# Test1.net
KiCad netlist of a schematic drawn in EAGLE
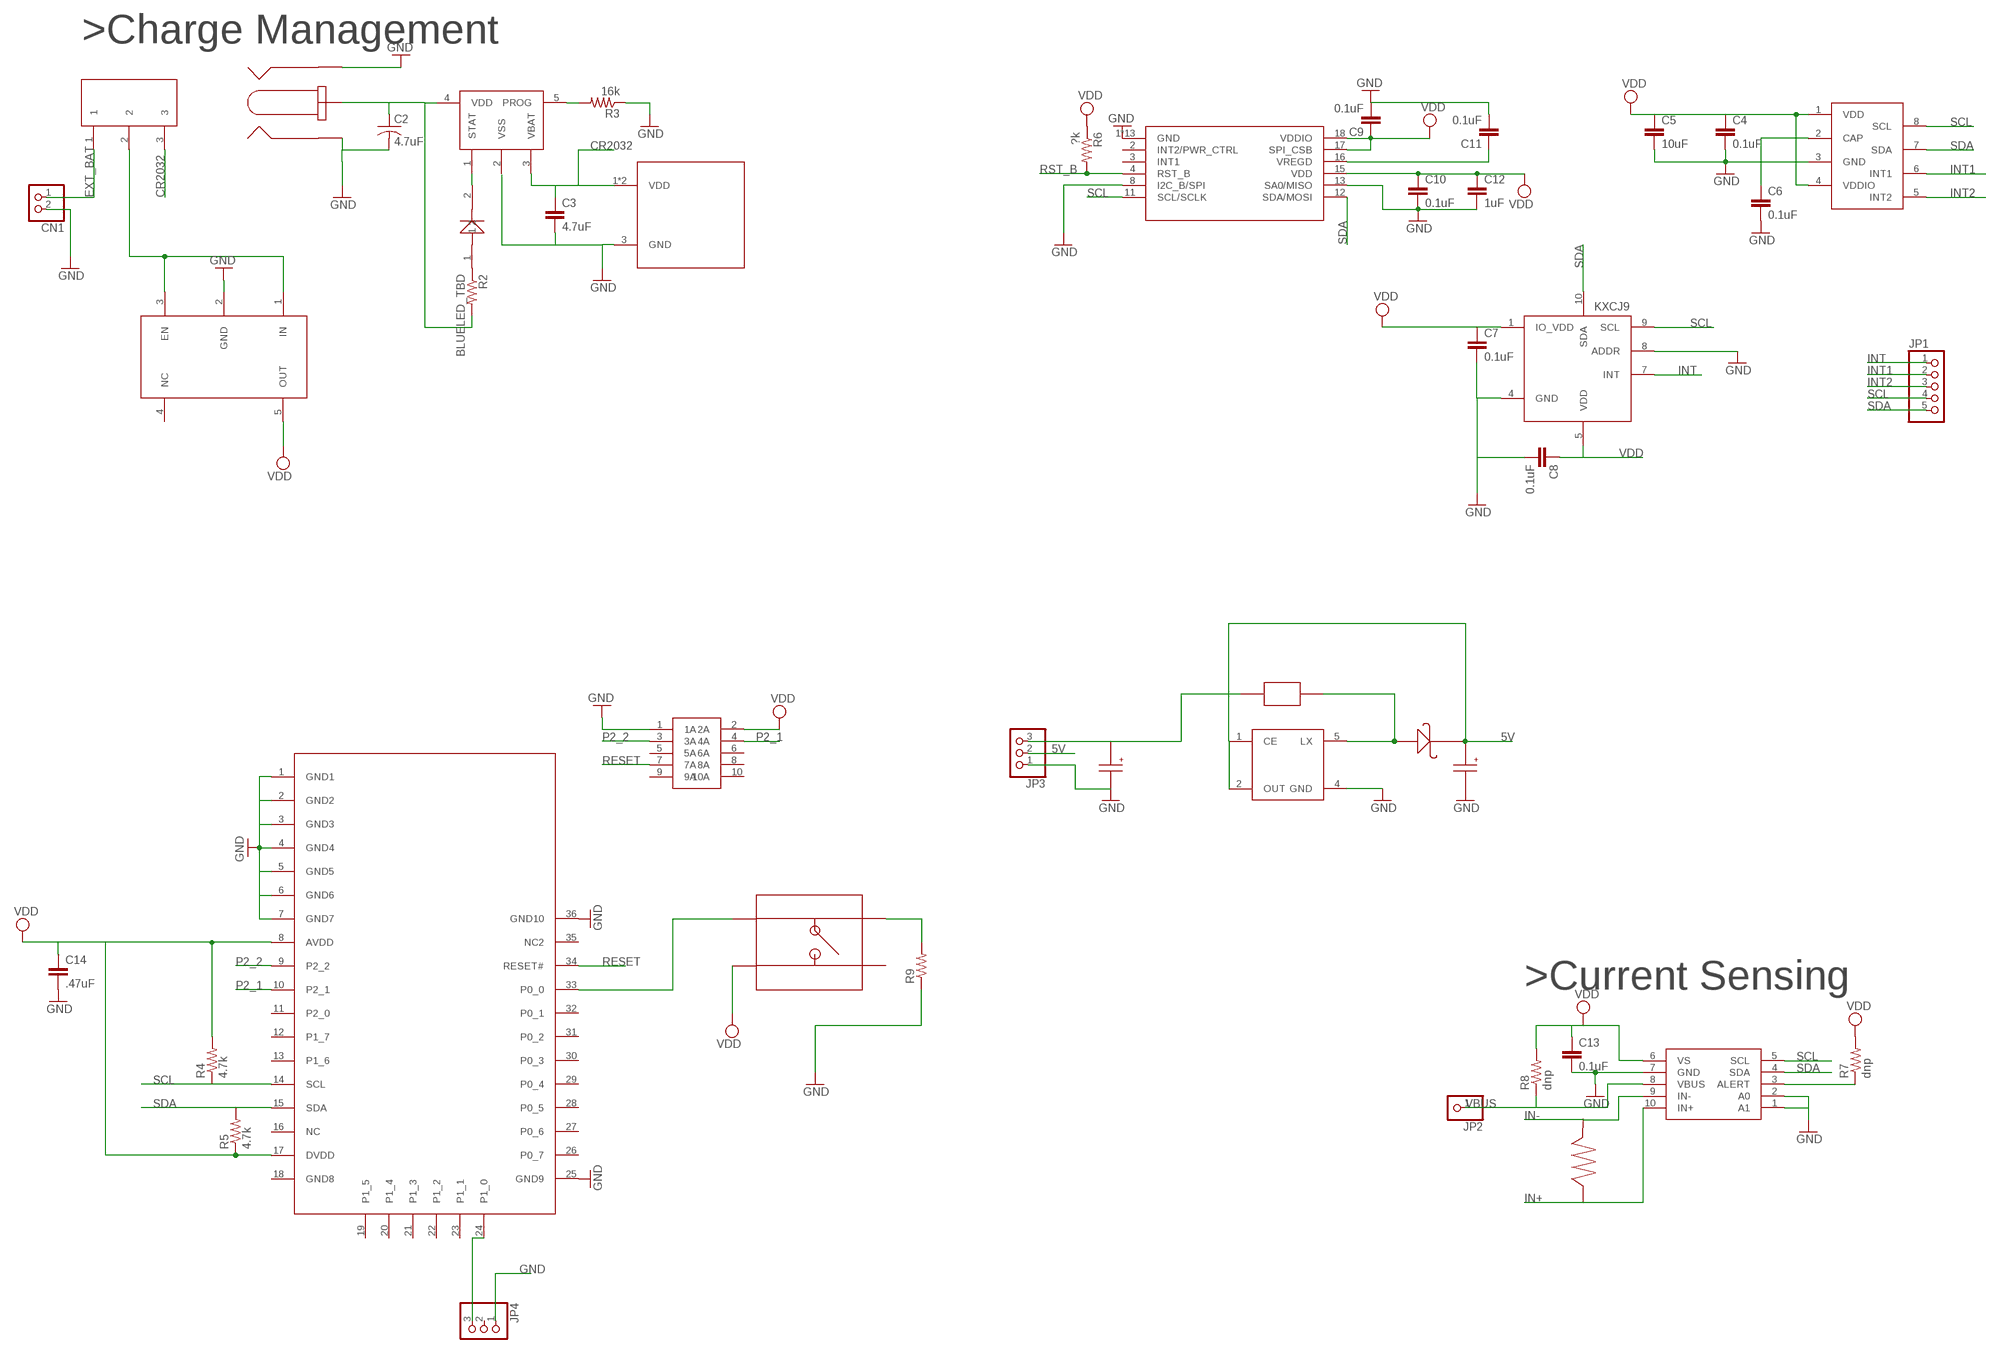
[diagram p0: schematic, sheet 1]

(export (version "E")
  (design (tool "Eeschema 10.0.6"))
  (components
    (comp (ref "C2")
      (value "4.7uF")
      (footprint "eagle-import:C0603")
      (libsource (lib "eagle-import") (part "C-USC0603"))
    )
    (comp (ref "C3")
      (value "4.7uF")
      (footprint "eagle-import:C0402")
      (libsource (lib "eagle-import") (part "C-EUC0402"))
    )
    (comp (ref "C4")
      (value "0.1uF")
      (footprint "eagle-import:C0402")
      (libsource (lib "eagle-import") (part "C-EUC0402"))
    )
    (comp (ref "C5")
      (value "10uF")
      (footprint "eagle-import:C0402")
      (libsource (lib "eagle-import") (part "C-EUC0402"))
    )
    (comp (ref "C6")
      (value "0.1uF")
      (footprint "eagle-import:C0402")
      (libsource (lib "eagle-import") (part "C-EUC0402"))
    )
    (comp (ref "C7")
      (value "0.1uF")
      (footprint "eagle-import:C0402")
      (libsource (lib "eagle-import") (part "C-EUC0402"))
    )
    (comp (ref "C8")
      (value "0.1uF")
      (footprint "eagle-import:C0402")
      (libsource (lib "eagle-import") (part "C-EUC0402"))
    )
    (comp (ref "C9")
      (value "0.1uF")
      (footprint "eagle-import:C0402")
      (libsource (lib "eagle-import") (part "C-EUC0402"))
    )
    (comp (ref "C10")
      (value "0.1uF")
      (footprint "eagle-import:C0402")
      (libsource (lib "eagle-import") (part "C-EUC0402"))
    )
    (comp (ref "C11")
      (value "0.1uF")
      (footprint "eagle-import:C0402")
      (libsource (lib "eagle-import") (part "C-EUC0402"))
    )
    (comp (ref "C12")
      (value "1uF")
      (footprint "eagle-import:C0402")
      (libsource (lib "eagle-import") (part "C-EUC0402"))
    )
    (comp (ref "C13")
      (value "0.1uF")
      (footprint "eagle-import:C0402")
      (libsource (lib "eagle-import") (part "C-EUC0402"))
    )
    (comp (ref "C14")
      (value ".47uF")
      (footprint "eagle-import:C0402")
      (libsource (lib "eagle-import") (part "C-EUC0402"))
    )
    (comp (ref "CN1")
      (value "JST_2PIN-THM")
      (footprint "eagle-import:JST-PH-2-THM")
      (libsource (lib "eagle-import") (part "JST_2PIN-THM"))
    )
    (comp (ref "JP1")
      (value "PINHD-1X5")
      (footprint "eagle-import:1X05")
      (libsource (lib "eagle-import") (part "PINHD-1X5"))
    )
    (comp (ref "JP2")
      (value "PINHD-1X1")
      (footprint "eagle-import:1X01")
      (libsource (lib "eagle-import") (part "PINHD-1X1"))
    )
    (comp (ref "JP3")
      (value "PINHD-1X3")
      (footprint "eagle-import:1X03")
      (libsource (lib "eagle-import") (part "PINHD-1X3"))
    )
    (comp (ref "JP4")
      (value "PINHD-1X3/90")
      (footprint "eagle-import:1X03_90")
      (libsource (lib "eagle-import") (part "PINHD-1X3/90"))
    )
    (comp (ref "R2")
      (value "BLUELED_TBD")
      (footprint "eagle-import:R0402")
      (libsource (lib "eagle-import") (part "R-US_R0402"))
    )
    (comp (ref "R3")
      (value "16k")
      (footprint "eagle-import:R0402")
      (libsource (lib "eagle-import") (part "R-US_R0402"))
    )
    (comp (ref "R4")
      (value "4.7k")
      (footprint "eagle-import:R0402")
      (libsource (lib "eagle-import") (part "R-US_R0402"))
    )
    (comp (ref "R5")
      (value "4.7k")
      (footprint "eagle-import:R0402")
      (libsource (lib "eagle-import") (part "R-US_R0402"))
    )
    (comp (ref "R6")
      (value "?k")
      (footprint "eagle-import:R0402")
      (libsource (lib "eagle-import") (part "R-US_R0402"))
    )
    (comp (ref "R7")
      (value "dnp")
      (footprint "eagle-import:R0402")
      (libsource (lib "eagle-import") (part "R-US_R0402"))
    )
    (comp (ref "R8")
      (value "dnp")
      (footprint "eagle-import:R0402")
      (libsource (lib "eagle-import") (part "R-US_R0402"))
    )
    (comp (ref "R9")
      (value "R-US_R0402")
      (footprint "eagle-import:R0402")
      (libsource (lib "eagle-import") (part "R-US_R0402"))
    )
    (comp (ref "U$1")
      (value "BAT-HLD-001")
      (footprint "eagle-import:BAT-HLD-001")
      (libsource (lib "eagle-import") (part "BAT-HLD-001"))
    )
    (comp (ref "U$2")
      (value "INA226")
      (footprint "eagle-import:INA226")
      (libsource (lib "eagle-import") (part "INA226"))
    )
    (comp (ref "U$3")
      (value "FXAS21002")
      (footprint "eagle-import:FXAS21002")
      (libsource (lib "eagle-import") (part "FXAS21002"))
    )
    (comp (ref "U$4")
      (value "PJ-040")
      (footprint "eagle-import:PJ-040")
      (libsource (lib "eagle-import") (part "PJ-040"))
    )
    (comp (ref "U$5")
      (value "PTS840")
      (footprint "eagle-import:PTS840")
      (libsource (lib "eagle-import") (part "PTS840"))
    )
    (comp (ref "U$6")
      (value "CD54NP-470LC")
      (footprint "eagle-import:CD54NP-470LC")
      (libsource (lib "eagle-import") (part "CD54NP-470LC"))
    )
    (comp (ref "U$7")
      (value "MRB0520LT1G")
      (footprint "eagle-import:SOD-323F")
      (libsource (lib "eagle-import") (part "MRB0520LT1G"))
    )
    (comp (ref "U$8")
      (value "MIC5203")
      (footprint "eagle-import:SOT23-5L")
      (libsource (lib "eagle-import") (part "MIC5203"))
    )
    (comp (ref "U$9")
      (value "MLP3115A2")
      (footprint "eagle-import:MLP3115A2")
      (libsource (lib "eagle-import") (part "MLP3115A2"))
    )
    (comp (ref "U$10")
      (value "RIBBON_10POS_MALE")
      (footprint "eagle-import:RIBBON_10POS_MALE")
      (libsource (lib "eagle-import") (part "RIBBON_10POS_MALE"))
    )
    (comp (ref "U$11")
      (value "BLE113")
      (footprint "eagle-import:BLUEGIGA")
      (libsource (lib "eagle-import") (part "BLE113"))
    )
    (comp (ref "U$12")
      (value "SPDT_THRU")
      (footprint "eagle-import:SPDT_THRU")
      (libsource (lib "eagle-import") (part "SPDT_THRU"))
    )
    (comp (ref "U$13")
      (value "KXCJ9")
      (footprint "eagle-import:KXCJ9")
      (libsource (lib "eagle-import") (part "KXCJ9"))
    )
    (comp (ref "U$14")
      (value "LTST-C190KRKT")
      (footprint "eagle-import:LTST-C190KRKT")
      (libsource (lib "eagle-import") (part "LTST-C190KRKT"))
    )
    (comp (ref "U$15")
      (value "ERJ-MS6SFM50U")
      (footprint "eagle-import:ERJ-MS6SFM50U")
      (libsource (lib "eagle-import") (part "ERJ-MS6SFM50U"))
    )
    (comp (ref "U$16")
      (value "MCP73831")
      (footprint "eagle-import:MCP73831")
      (libsource (lib "eagle-import") (part "MCP73831"))
    )
    (comp (ref "U$17")
      (value "NCP1402")
      (footprint "eagle-import:SOT23-5L")
      (libsource (lib "eagle-import") (part "NCP1402"))
    )
    (comp (ref "U$18")
      (value "10uF")
      (footprint "eagle-import:C2413")
      (libsource (lib "eagle-import") (part "C2413"))
    )
    (comp (ref "U$19")
      (value "68uF")
      (footprint "eagle-import:C2413")
      (libsource (lib "eagle-import") (part "C2413"))
    )
  )
  (nets
    (net (code "1") (name "/5V") (class "Default")
      (node (ref "JP3") (pin "2") (pinfunction "2_2") (pintype "passive"))
      (node (ref "U$17") (pin "1") (pinfunction "CE_1") (pintype "bidirectional"))
      (node (ref "U$17") (pin "2") (pinfunction "OUT_2") (pintype "bidirectional"))
      (node (ref "U$19") (pin "1") (pinfunction "P$1_1") (pintype "bidirectional"))
      (node (ref "U$7") (pin "2") (pinfunction "P$2_2") (pintype "bidirectional"))
    )
    (net (code "2") (name "/CR2032") (class "Default")
      (node (ref "C3") (pin "1") (pinfunction "1_1") (pintype "passive"))
      (node (ref "U$1") (pin "1") (pinfunction "VDD_1") (pintype "bidirectional"))
      (node (ref "U$1") (pin "2") (pinfunction "VDD_2") (pintype "bidirectional"))
      (node (ref "U$12") (pin "3") (pinfunction "3_3") (pintype "bidirectional"))
      (node (ref "U$16") (pin "3") (pinfunction "VBAT_3") (pintype "bidirectional"))
    )
    (net (code "3") (name "/EXT_BAT") (class "Default")
      (node (ref "CN1") (pin "1") (pinfunction "2_1") (pintype "passive"))
      (node (ref "U$12") (pin "1") (pinfunction "1_1") (pintype "bidirectional"))
    )
    (net (code "4") (name "/IN+") (class "Default")
      (node (ref "U$15") (pin "1") (pinfunction "P$1_1") (pintype "bidirectional"))
      (node (ref "U$2") (pin "10") (pinfunction "IN+_10") (pintype "bidirectional"))
    )
    (net (code "5") (name "/IN-") (class "Default")
      (node (ref "U$15") (pin "2") (pinfunction "P$2_2") (pintype "bidirectional"))
      (node (ref "U$2") (pin "9") (pinfunction "IN-_9") (pintype "bidirectional"))
    )
    (net (code "6") (name "/INT") (class "Default")
      (node (ref "JP1") (pin "1") (pinfunction "1_1") (pintype "passive"))
      (node (ref "U$13") (pin "7") (pinfunction "INT_7") (pintype "bidirectional"))
    )
    (net (code "7") (name "/INT1") (class "Default")
      (node (ref "JP1") (pin "2") (pinfunction "2_2") (pintype "passive"))
      (node (ref "U$9") (pin "6") (pinfunction "INT1_6") (pintype "bidirectional"))
    )
    (net (code "8") (name "/INT2") (class "Default")
      (node (ref "JP1") (pin "3") (pinfunction "3_3") (pintype "passive"))
      (node (ref "U$9") (pin "5") (pinfunction "INT2_5") (pintype "bidirectional"))
    )
    (net (code "9") (name "/P2_1") (class "Default")
      (node (ref "U$10") (pin "4") (pinfunction "4A_4") (pintype "bidirectional"))
      (node (ref "U$11") (pin "10") (pinfunction "P2_1_10") (pintype "bidirectional"))
    )
    (net (code "10") (name "/P2_2") (class "Default")
      (node (ref "U$10") (pin "3") (pinfunction "3A_3") (pintype "bidirectional"))
      (node (ref "U$11") (pin "9") (pinfunction "P2_2_9") (pintype "bidirectional"))
    )
    (net (code "11") (name "/RESET") (class "Default")
      (node (ref "U$10") (pin "7") (pinfunction "7A_7") (pintype "bidirectional"))
      (node (ref "U$11") (pin "34") (pinfunction "RESET#_34") (pintype "bidirectional"))
    )
    (net (code "12") (name "/RST_B") (class "Default")
      (node (ref "R6") (pin "2") (pinfunction "2_2") (pintype "passive"))
      (node (ref "U$3") (pin "4") (pinfunction "RST_B_4") (pintype "bidirectional"))
    )
    (net (code "13") (name "/SCL") (class "Default")
      (node (ref "JP1") (pin "4") (pinfunction "4_4") (pintype "passive"))
      (node (ref "R4") (pin "1") (pinfunction "1_1") (pintype "passive"))
      (node (ref "U$11") (pin "14") (pinfunction "SCL_14") (pintype "bidirectional"))
      (node (ref "U$13") (pin "9") (pinfunction "SCL_9") (pintype "bidirectional"))
      (node (ref "U$2") (pin "5") (pinfunction "SCL_5") (pintype "bidirectional"))
      (node (ref "U$3") (pin "11") (pinfunction "SCL/SCLK_11") (pintype "bidirectional"))
      (node (ref "U$9") (pin "8") (pinfunction "SCL_8") (pintype "bidirectional"))
    )
    (net (code "14") (name "/SDA") (class "Default")
      (node (ref "JP1") (pin "5") (pinfunction "5_5") (pintype "passive"))
      (node (ref "R5") (pin "2") (pinfunction "2_2") (pintype "passive"))
      (node (ref "U$11") (pin "15") (pinfunction "SDA_15") (pintype "bidirectional"))
      (node (ref "U$13") (pin "10") (pinfunction "SDA_10") (pintype "bidirectional"))
      (node (ref "U$2") (pin "4") (pinfunction "SDA_4") (pintype "bidirectional"))
      (node (ref "U$3") (pin "12") (pinfunction "SDA/MOSI_12") (pintype "bidirectional"))
      (node (ref "U$9") (pin "7") (pinfunction "SDA_7") (pintype "bidirectional"))
    )
    (net (code "15") (name "/VBUS") (class "Default")
      (node (ref "JP2") (pin "1") (pinfunction "1_1") (pintype "passive"))
      (node (ref "R8") (pin "1") (pinfunction "1_1") (pintype "passive"))
      (node (ref "U$2") (pin "8") (pinfunction "VBUS_8") (pintype "bidirectional"))
    )
    (net (code "16") (name "GND") (class "Default")
      (node (ref "C10") (pin "2") (pinfunction "2_2") (pintype "passive"))
      (node (ref "C11") (pin "2") (pinfunction "2_2") (pintype "passive"))
      (node (ref "C12") (pin "2") (pinfunction "2_2") (pintype "passive"))
      (node (ref "C13") (pin "2") (pinfunction "2_2") (pintype "passive"))
      (node (ref "C14") (pin "2") (pinfunction "2_2") (pintype "passive"))
      (node (ref "C2") (pin "2") (pinfunction "2_2") (pintype "passive"))
      (node (ref "C3") (pin "2") (pinfunction "2_2") (pintype "passive"))
      (node (ref "C4") (pin "2") (pinfunction "2_2") (pintype "passive"))
      (node (ref "C5") (pin "2") (pinfunction "2_2") (pintype "passive"))
      (node (ref "C6") (pin "2") (pinfunction "2_2") (pintype "passive"))
      (node (ref "C7") (pin "2") (pinfunction "2_2") (pintype "passive"))
      (node (ref "C8") (pin "2") (pinfunction "2_2") (pintype "passive"))
      (node (ref "C9") (pin "2") (pinfunction "2_2") (pintype "passive"))
      (node (ref "CN1") (pin "2") (pinfunction "1_2") (pintype "passive"))
      (node (ref "JP3") (pin "1") (pinfunction "1_1") (pintype "passive"))
      (node (ref "JP4") (pin "1") (pinfunction "1_1") (pintype "passive"))
      (node (ref "R3") (pin "1") (pinfunction "1_1") (pintype "passive"))
      (node (ref "R9") (pin "1") (pinfunction "1_1") (pintype "passive"))
      (node (ref "U$1") (pin "3") (pinfunction "GND_3") (pintype "bidirectional"))
      (node (ref "U$10") (pin "1") (pinfunction "1A_1") (pintype "bidirectional"))
      (node (ref "U$11") (pin "1") (pinfunction "GND1_1") (pintype "bidirectional"))
      (node (ref "U$11") (pin "2") (pinfunction "GND2_2") (pintype "bidirectional"))
      (node (ref "U$11") (pin "25") (pinfunction "GND9_25") (pintype "bidirectional"))
      (node (ref "U$11") (pin "3") (pinfunction "GND3_3") (pintype "bidirectional"))
      (node (ref "U$11") (pin "36") (pinfunction "GND10_36") (pintype "bidirectional"))
      (node (ref "U$11") (pin "4") (pinfunction "GND4_4") (pintype "bidirectional"))
      (node (ref "U$11") (pin "5") (pinfunction "GND5_5") (pintype "bidirectional"))
      (node (ref "U$11") (pin "6") (pinfunction "GND6_6") (pintype "bidirectional"))
      (node (ref "U$11") (pin "7") (pinfunction "GND7_7") (pintype "bidirectional"))
      (node (ref "U$13") (pin "4") (pinfunction "GND_4") (pintype "bidirectional"))
      (node (ref "U$13") (pin "8") (pinfunction "ADDR_8") (pintype "bidirectional"))
      (node (ref "U$17") (pin "4") (pinfunction "GND_4") (pintype "bidirectional"))
      (node (ref "U$18") (pin "2") (pinfunction "P$2_2") (pintype "bidirectional"))
      (node (ref "U$19") (pin "2") (pinfunction "P$2_2") (pintype "bidirectional"))
      (node (ref "U$2") (pin "1") (pinfunction "A1_1") (pintype "bidirectional"))
      (node (ref "U$2") (pin "2") (pinfunction "A0_2") (pintype "bidirectional"))
      (node (ref "U$2") (pin "7") (pinfunction "GND_7") (pintype "bidirectional"))
      (node (ref "U$3") (pin "1") (pinfunction "GND_1") (pintype "bidirectional"))
      (node (ref "U$3") (pin "10") (pinfunction "GND_10") (pintype "bidirectional"))
      (node (ref "U$3") (pin "13") (pinfunction "SA0/MISO_13") (pintype "bidirectional"))
      (node (ref "U$3") (pin "14") (pinfunction "GND_14") (pintype "bidirectional"))
      (node (ref "U$3") (pin "19") (pinfunction "GND_19") (pintype "bidirectional"))
      (node (ref "U$3") (pin "20") (pinfunction "GND_20") (pintype "bidirectional"))
      (node (ref "U$3") (pin "21") (pinfunction "GND_21") (pintype "bidirectional"))
      (node (ref "U$3") (pin "22") (pinfunction "GND_22") (pintype "bidirectional"))
      (node (ref "U$3") (pin "23") (pinfunction "GND_23") (pintype "bidirectional"))
      (node (ref "U$3") (pin "24") (pinfunction "GND_24") (pintype "bidirectional"))
      (node (ref "U$3") (pin "5") (pinfunction "GND_5") (pintype "bidirectional"))
      (node (ref "U$3") (pin "6") (pinfunction "GND_6") (pintype "bidirectional"))
      (node (ref "U$3") (pin "7") (pinfunction "GND_7") (pintype "bidirectional"))
      (node (ref "U$3") (pin "8") (pinfunction "I2C_B/SPI_8") (pintype "bidirectional"))
      (node (ref "U$3") (pin "9") (pinfunction "GND_9") (pintype "bidirectional"))
      (node (ref "U$4") (pin "2") (pinfunction "2_2") (pintype "bidirectional"))
      (node (ref "U$4") (pin "3") (pinfunction "3_3") (pintype "bidirectional"))
      (node (ref "U$8") (pin "2") (pinfunction "GND_2") (pintype "bidirectional"))
      (node (ref "U$9") (pin "3") (pinfunction "GND_3") (pintype "bidirectional"))
    )
    (net (code "17") (name "Net-(R2-Pad1)") (class "Default")
      (node (ref "R2") (pin "1") (pinfunction "1_1") (pintype "passive"))
      (node (ref "U$14") (pin "1") (pinfunction "1_1") (pintype "bidirectional"))
    )
    (net (code "18") (name "Net-(R9-Pad2)") (class "Default")
      (node (ref "R9") (pin "2") (pinfunction "2_2") (pintype "passive"))
      (node (ref "U$5") (pin "3") (pinfunction "3_3") (pintype "bidirectional"))
    )
    (net (code "19") (name "Net-(U$2-ALERT)") (class "Default")
      (node (ref "R7") (pin "1") (pinfunction "1_1") (pintype "passive"))
      (node (ref "U$2") (pin "3") (pinfunction "ALERT_3") (pintype "bidirectional"))
    )
    (net (code "20") (name "Net-(U$3-VREGD)") (class "Default")
      (node (ref "C11") (pin "1") (pinfunction "1_1") (pintype "passive"))
      (node (ref "U$3") (pin "16") (pinfunction "VREGD_16") (pintype "bidirectional"))
    )
    (net (code "21") (name "Net-(U$8-EN)") (class "Default")
      (node (ref "U$12") (pin "2") (pinfunction "2_2") (pintype "bidirectional"))
      (node (ref "U$8") (pin "1") (pinfunction "IN_1") (pintype "bidirectional"))
      (node (ref "U$8") (pin "3") (pinfunction "EN_3") (pintype "bidirectional"))
    )
    (net (code "22") (name "Net-(U$9-CAP)") (class "Default")
      (node (ref "C6") (pin "1") (pinfunction "1_1") (pintype "passive"))
      (node (ref "U$9") (pin "2") (pinfunction "CAP_2") (pintype "bidirectional"))
    )
    (net (code "23") (name "Net-(U$11-P0_0)") (class "Default")
      (node (ref "U$11") (pin "33") (pinfunction "P0_0_33") (pintype "bidirectional"))
      (node (ref "U$5") (pin "4") (pinfunction "4_4") (pintype "bidirectional"))
    )
    (net (code "24") (name "Net-(U$11-P1_0)") (class "Default")
      (node (ref "JP4") (pin "3") (pinfunction "3_3") (pintype "passive"))
      (node (ref "U$11") (pin "24") (pinfunction "P1_0_24") (pintype "bidirectional"))
    )
    (net (code "25") (name "Net-(U$16-PROG)") (class "Default")
      (node (ref "R3") (pin "2") (pinfunction "2_2") (pintype "passive"))
      (node (ref "U$16") (pin "5") (pinfunction "PROG_5") (pintype "bidirectional"))
    )
    (net (code "26") (name "Net-(U$16-STAT)") (class "Default")
      (node (ref "U$14") (pin "2") (pinfunction "2_2") (pintype "bidirectional"))
      (node (ref "U$16") (pin "1") (pinfunction "STAT_1") (pintype "bidirectional"))
    )
    (net (code "27") (name "Net-(U$16-VDD)") (class "Default")
      (node (ref "C2") (pin "1") (pinfunction "1_1") (pintype "passive"))
      (node (ref "R2") (pin "2") (pinfunction "2_2") (pintype "passive"))
      (node (ref "U$16") (pin "4") (pinfunction "VDD_4") (pintype "bidirectional"))
      (node (ref "U$4") (pin "1") (pinfunction "1_1") (pintype "bidirectional"))
    )
    (net (code "28") (name "Net-(U$17-LX)") (class "Default")
      (node (ref "U$17") (pin "5") (pinfunction "LX_5") (pintype "bidirectional"))
      (node (ref "U$6") (pin "2") (pinfunction "P$2_2") (pintype "bidirectional"))
      (node (ref "U$7") (pin "1") (pinfunction "P$1_1") (pintype "bidirectional"))
    )
    (net (code "29") (name "Net-(U$18-P$1)") (class "Default")
      (node (ref "JP3") (pin "3") (pinfunction "3_3") (pintype "passive"))
      (node (ref "U$18") (pin "1") (pinfunction "P$1_1") (pintype "bidirectional"))
      (node (ref "U$6") (pin "1") (pinfunction "P$1_1") (pintype "bidirectional"))
    )
    (net (code "30") (name "VDD") (class "Default")
      (node (ref "C10") (pin "1") (pinfunction "1_1") (pintype "passive"))
      (node (ref "C12") (pin "1") (pinfunction "1_1") (pintype "passive"))
      (node (ref "C13") (pin "1") (pinfunction "1_1") (pintype "passive"))
      (node (ref "C14") (pin "1") (pinfunction "1_1") (pintype "passive"))
      (node (ref "C4") (pin "1") (pinfunction "1_1") (pintype "passive"))
      (node (ref "C5") (pin "1") (pinfunction "1_1") (pintype "passive"))
      (node (ref "C7") (pin "1") (pinfunction "1_1") (pintype "passive"))
      (node (ref "C8") (pin "1") (pinfunction "1_1") (pintype "passive"))
      (node (ref "C9") (pin "1") (pinfunction "1_1") (pintype "passive"))
      (node (ref "R4") (pin "2") (pinfunction "2_2") (pintype "passive"))
      (node (ref "R5") (pin "1") (pinfunction "1_1") (pintype "passive"))
      (node (ref "R6") (pin "1") (pinfunction "1_1") (pintype "passive"))
      (node (ref "R7") (pin "2") (pinfunction "2_2") (pintype "passive"))
      (node (ref "R8") (pin "2") (pinfunction "2_2") (pintype "passive"))
      (node (ref "U$10") (pin "2") (pinfunction "2A_2") (pintype "bidirectional"))
      (node (ref "U$11") (pin "17") (pinfunction "DVDD_17") (pintype "bidirectional"))
      (node (ref "U$11") (pin "8") (pinfunction "AVDD_8") (pintype "bidirectional"))
      (node (ref "U$13") (pin "1") (pinfunction "IO_VDD_1") (pintype "bidirectional"))
      (node (ref "U$13") (pin "5") (pinfunction "VDD_5") (pintype "bidirectional"))
      (node (ref "U$2") (pin "6") (pinfunction "VS_6") (pintype "bidirectional"))
      (node (ref "U$3") (pin "15") (pinfunction "VDD_15") (pintype "bidirectional"))
      (node (ref "U$3") (pin "17") (pinfunction "SPI_CSB_17") (pintype "bidirectional"))
      (node (ref "U$3") (pin "18") (pinfunction "VDDIO_18") (pintype "bidirectional"))
      (node (ref "U$5") (pin "2") (pinfunction "2_2") (pintype "bidirectional"))
      (node (ref "U$8") (pin "5") (pinfunction "OUT_5") (pintype "bidirectional"))
      (node (ref "U$9") (pin "1") (pinfunction "VDD_1") (pintype "bidirectional"))
      (node (ref "U$9") (pin "4") (pinfunction "VDDIO_4") (pintype "bidirectional"))
    )
    (net (code "31") (name "unconnected-(JP4-Pad2)") (class "Default")
      (node (ref "JP4") (pin "2") (pinfunction "2_2") (pintype "passive"))
    )
    (net (code "32") (name "unconnected-(U$3-INT1-Pad3)") (class "Default")
      (node (ref "U$3") (pin "3") (pinfunction "INT1_3") (pintype "bidirectional"))
    )
    (net (code "33") (name "unconnected-(U$3-INT2{slash}PWR_CTRL-Pad2)") (class "Default")
      (node (ref "U$3") (pin "2") (pinfunction "INT2/PWR_CTRL_2") (pintype "bidirectional"))
    )
    (net (code "34") (name "unconnected-(U$5-Pad1)") (class "Default")
      (node (ref "U$5") (pin "1") (pinfunction "1_1") (pintype "bidirectional"))
    )
    (net (code "35") (name "unconnected-(U$8-NC-Pad4)") (class "Default")
      (node (ref "U$8") (pin "4") (pinfunction "NC_4") (pintype "bidirectional"))
    )
    (net (code "36") (name "unconnected-(U$10-5A-Pad5)") (class "Default")
      (node (ref "U$10") (pin "5") (pinfunction "5A_5") (pintype "bidirectional"))
    )
    (net (code "37") (name "unconnected-(U$10-6A-Pad6)") (class "Default")
      (node (ref "U$10") (pin "6") (pinfunction "6A_6") (pintype "bidirectional"))
    )
    (net (code "38") (name "unconnected-(U$10-8A-Pad8)") (class "Default")
      (node (ref "U$10") (pin "8") (pinfunction "8A_8") (pintype "bidirectional"))
    )
    (net (code "39") (name "unconnected-(U$10-9A-Pad9)") (class "Default")
      (node (ref "U$10") (pin "9") (pinfunction "9A_9") (pintype "bidirectional"))
    )
    (net (code "40") (name "unconnected-(U$10-10A-Pad10)") (class "Default")
      (node (ref "U$10") (pin "10") (pinfunction "10A_10") (pintype "bidirectional"))
    )
    (net (code "41") (name "unconnected-(U$11-GND8-Pad18)") (class "Default")
      (node (ref "U$11") (pin "18") (pinfunction "GND8_18") (pintype "bidirectional"))
    )
    (net (code "42") (name "unconnected-(U$11-NC-Pad16)") (class "Default")
      (node (ref "U$11") (pin "16") (pinfunction "NC_16") (pintype "bidirectional"))
    )
    (net (code "43") (name "unconnected-(U$11-NC2-Pad35)") (class "Default")
      (node (ref "U$11") (pin "35") (pinfunction "NC2_35") (pintype "bidirectional"))
    )
    (net (code "44") (name "unconnected-(U$11-P0_1-Pad32)") (class "Default")
      (node (ref "U$11") (pin "32") (pinfunction "P0_1_32") (pintype "bidirectional"))
    )
    (net (code "45") (name "unconnected-(U$11-P0_2-Pad31)") (class "Default")
      (node (ref "U$11") (pin "31") (pinfunction "P0_2_31") (pintype "bidirectional"))
    )
    (net (code "46") (name "unconnected-(U$11-P0_3-Pad30)") (class "Default")
      (node (ref "U$11") (pin "30") (pinfunction "P0_3_30") (pintype "bidirectional"))
    )
    (net (code "47") (name "unconnected-(U$11-P0_4-Pad29)") (class "Default")
      (node (ref "U$11") (pin "29") (pinfunction "P0_4_29") (pintype "bidirectional"))
    )
    (net (code "48") (name "unconnected-(U$11-P0_5-Pad28)") (class "Default")
      (node (ref "U$11") (pin "28") (pinfunction "P0_5_28") (pintype "bidirectional"))
    )
    (net (code "49") (name "unconnected-(U$11-P0_6-Pad27)") (class "Default")
      (node (ref "U$11") (pin "27") (pinfunction "P0_6_27") (pintype "bidirectional"))
    )
    (net (code "50") (name "unconnected-(U$11-P0_7-Pad26)") (class "Default")
      (node (ref "U$11") (pin "26") (pinfunction "P0_7_26") (pintype "bidirectional"))
    )
    (net (code "51") (name "unconnected-(U$11-P1_1-Pad23)") (class "Default")
      (node (ref "U$11") (pin "23") (pinfunction "P1_1_23") (pintype "bidirectional"))
    )
    (net (code "52") (name "unconnected-(U$11-P1_2-Pad22)") (class "Default")
      (node (ref "U$11") (pin "22") (pinfunction "P1_2_22") (pintype "bidirectional"))
    )
    (net (code "53") (name "unconnected-(U$11-P1_3-Pad21)") (class "Default")
      (node (ref "U$11") (pin "21") (pinfunction "P1_3_21") (pintype "bidirectional"))
    )
    (net (code "54") (name "unconnected-(U$11-P1_4-Pad20)") (class "Default")
      (node (ref "U$11") (pin "20") (pinfunction "P1_4_20") (pintype "bidirectional"))
    )
    (net (code "55") (name "unconnected-(U$11-P1_5-Pad19)") (class "Default")
      (node (ref "U$11") (pin "19") (pinfunction "P1_5_19") (pintype "bidirectional"))
    )
    (net (code "56") (name "unconnected-(U$11-P1_6-Pad13)") (class "Default")
      (node (ref "U$11") (pin "13") (pinfunction "P1_6_13") (pintype "bidirectional"))
    )
    (net (code "57") (name "unconnected-(U$11-P1_7-Pad12)") (class "Default")
      (node (ref "U$11") (pin "12") (pinfunction "P1_7_12") (pintype "bidirectional"))
    )
    (net (code "58") (name "unconnected-(U$11-P2_0-Pad11)") (class "Default")
      (node (ref "U$11") (pin "11") (pinfunction "P2_0_11") (pintype "bidirectional"))
    )
    (net (code "59") (name "unconnected-(U$16-VSS-Pad2)") (class "Default")
      (node (ref "U$16") (pin "2") (pinfunction "VSS_2") (pintype "bidirectional"))
    )
  )
)
